# Sheet1.net
KiCad netlist of a schematic drawn in Altium Designer
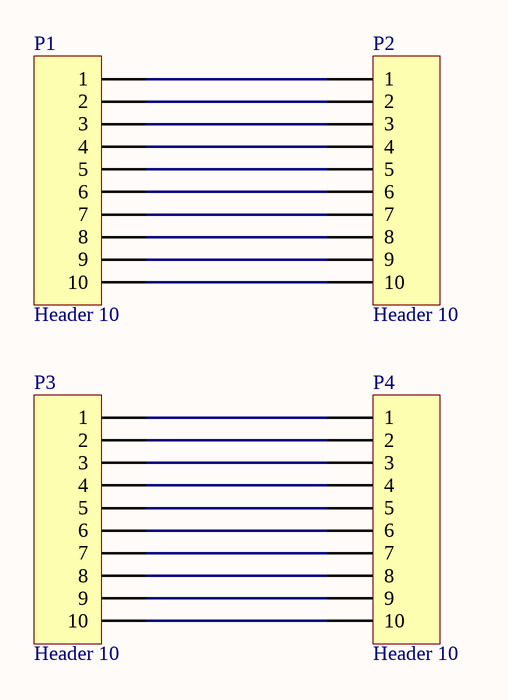
[diagram p0: Sheet1.SchDoc]

(export (version "E")
  (design (tool "Eeschema 10.0.6"))
  (components
    (comp (ref "P1")
      (value "Header 10")
      (footprint "HDR1X10")
      (description "Header, 10-Pin")
      (fields (field (name "PUBLISHER") "Altium Limited"))
      (libsource (lib "") (part "Header 10_1"))
    )
    (comp (ref "P2")
      (value "Header 10")
      (footprint "HDR1X10")
      (description "Header, 10-Pin")
      (fields (field (name "PUBLISHER") "Altium Limited"))
      (libsource (lib "Miscellaneous Connectors") (part "Header 10"))
    )
    (comp (ref "P3")
      (value "Header 10")
      (footprint "HDR1X10")
      (description "Header, 10-Pin")
      (fields (field (name "PUBLISHER") "Altium Limited"))
      (libsource (lib "") (part "Header 10_1"))
    )
    (comp (ref "P4")
      (value "Header 10")
      (footprint "HDR1X10")
      (description "Header, 10-Pin")
      (fields (field (name "PUBLISHER") "Altium Limited"))
      (libsource (lib "Miscellaneous Connectors") (part "Header 10"))
    )
  )
  (nets
    (net (code "1") (name "Net-(P1-Pad1)") (class "Default")
      (node (ref "P1") (pin "1") (pinfunction "1_1") (pintype "passive"))
      (node (ref "P2") (pin "1") (pinfunction "1_1") (pintype "passive"))
    )
    (net (code "2") (name "Net-(P1-Pad2)") (class "Default")
      (node (ref "P1") (pin "2") (pinfunction "2_2") (pintype "passive"))
      (node (ref "P2") (pin "2") (pinfunction "2_2") (pintype "passive"))
    )
    (net (code "3") (name "Net-(P1-Pad3)") (class "Default")
      (node (ref "P1") (pin "3") (pinfunction "3_3") (pintype "passive"))
      (node (ref "P2") (pin "3") (pinfunction "3_3") (pintype "passive"))
    )
    (net (code "4") (name "Net-(P1-Pad4)") (class "Default")
      (node (ref "P1") (pin "4") (pinfunction "4_4") (pintype "passive"))
      (node (ref "P2") (pin "4") (pinfunction "4_4") (pintype "passive"))
    )
    (net (code "5") (name "Net-(P1-Pad5)") (class "Default")
      (node (ref "P1") (pin "5") (pinfunction "5_5") (pintype "passive"))
      (node (ref "P2") (pin "5") (pinfunction "5_5") (pintype "passive"))
    )
    (net (code "6") (name "Net-(P1-Pad6)") (class "Default")
      (node (ref "P1") (pin "6") (pinfunction "6_6") (pintype "passive"))
      (node (ref "P2") (pin "6") (pinfunction "6_6") (pintype "passive"))
    )
    (net (code "7") (name "Net-(P1-Pad7)") (class "Default")
      (node (ref "P1") (pin "7") (pinfunction "7_7") (pintype "passive"))
      (node (ref "P2") (pin "7") (pinfunction "7_7") (pintype "passive"))
    )
    (net (code "8") (name "Net-(P1-Pad8)") (class "Default")
      (node (ref "P1") (pin "8") (pinfunction "8_8") (pintype "passive"))
      (node (ref "P2") (pin "8") (pinfunction "8_8") (pintype "passive"))
    )
    (net (code "9") (name "Net-(P1-Pad9)") (class "Default")
      (node (ref "P1") (pin "9") (pinfunction "9_9") (pintype "passive"))
      (node (ref "P2") (pin "9") (pinfunction "9_9") (pintype "passive"))
    )
    (net (code "10") (name "Net-(P1-Pad10)") (class "Default")
      (node (ref "P1") (pin "10") (pinfunction "10_10") (pintype "passive"))
      (node (ref "P2") (pin "10") (pinfunction "10_10") (pintype "passive"))
    )
    (net (code "11") (name "Net-(P3-Pad1)") (class "Default")
      (node (ref "P3") (pin "1") (pinfunction "1_1") (pintype "passive"))
      (node (ref "P4") (pin "1") (pinfunction "1_1") (pintype "passive"))
    )
    (net (code "12") (name "Net-(P3-Pad2)") (class "Default")
      (node (ref "P3") (pin "2") (pinfunction "2_2") (pintype "passive"))
      (node (ref "P4") (pin "2") (pinfunction "2_2") (pintype "passive"))
    )
    (net (code "13") (name "Net-(P3-Pad3)") (class "Default")
      (node (ref "P3") (pin "3") (pinfunction "3_3") (pintype "passive"))
      (node (ref "P4") (pin "3") (pinfunction "3_3") (pintype "passive"))
    )
    (net (code "14") (name "Net-(P3-Pad4)") (class "Default")
      (node (ref "P3") (pin "4") (pinfunction "4_4") (pintype "passive"))
      (node (ref "P4") (pin "4") (pinfunction "4_4") (pintype "passive"))
    )
    (net (code "15") (name "Net-(P3-Pad5)") (class "Default")
      (node (ref "P3") (pin "5") (pinfunction "5_5") (pintype "passive"))
      (node (ref "P4") (pin "5") (pinfunction "5_5") (pintype "passive"))
    )
    (net (code "16") (name "Net-(P3-Pad6)") (class "Default")
      (node (ref "P3") (pin "6") (pinfunction "6_6") (pintype "passive"))
      (node (ref "P4") (pin "6") (pinfunction "6_6") (pintype "passive"))
    )
    (net (code "17") (name "Net-(P3-Pad7)") (class "Default")
      (node (ref "P3") (pin "7") (pinfunction "7_7") (pintype "passive"))
      (node (ref "P4") (pin "7") (pinfunction "7_7") (pintype "passive"))
    )
    (net (code "18") (name "Net-(P3-Pad8)") (class "Default")
      (node (ref "P3") (pin "8") (pinfunction "8_8") (pintype "passive"))
      (node (ref "P4") (pin "8") (pinfunction "8_8") (pintype "passive"))
    )
    (net (code "19") (name "Net-(P3-Pad9)") (class "Default")
      (node (ref "P3") (pin "9") (pinfunction "9_9") (pintype "passive"))
      (node (ref "P4") (pin "9") (pinfunction "9_9") (pintype "passive"))
    )
    (net (code "20") (name "Net-(P3-Pad10)") (class "Default")
      (node (ref "P3") (pin "10") (pinfunction "10_10") (pintype "passive"))
      (node (ref "P4") (pin "10") (pinfunction "10_10") (pintype "passive"))
    )
  )
)
